# ExtendBoard.net
KiCad netlist of a schematic drawn in Altium Designer
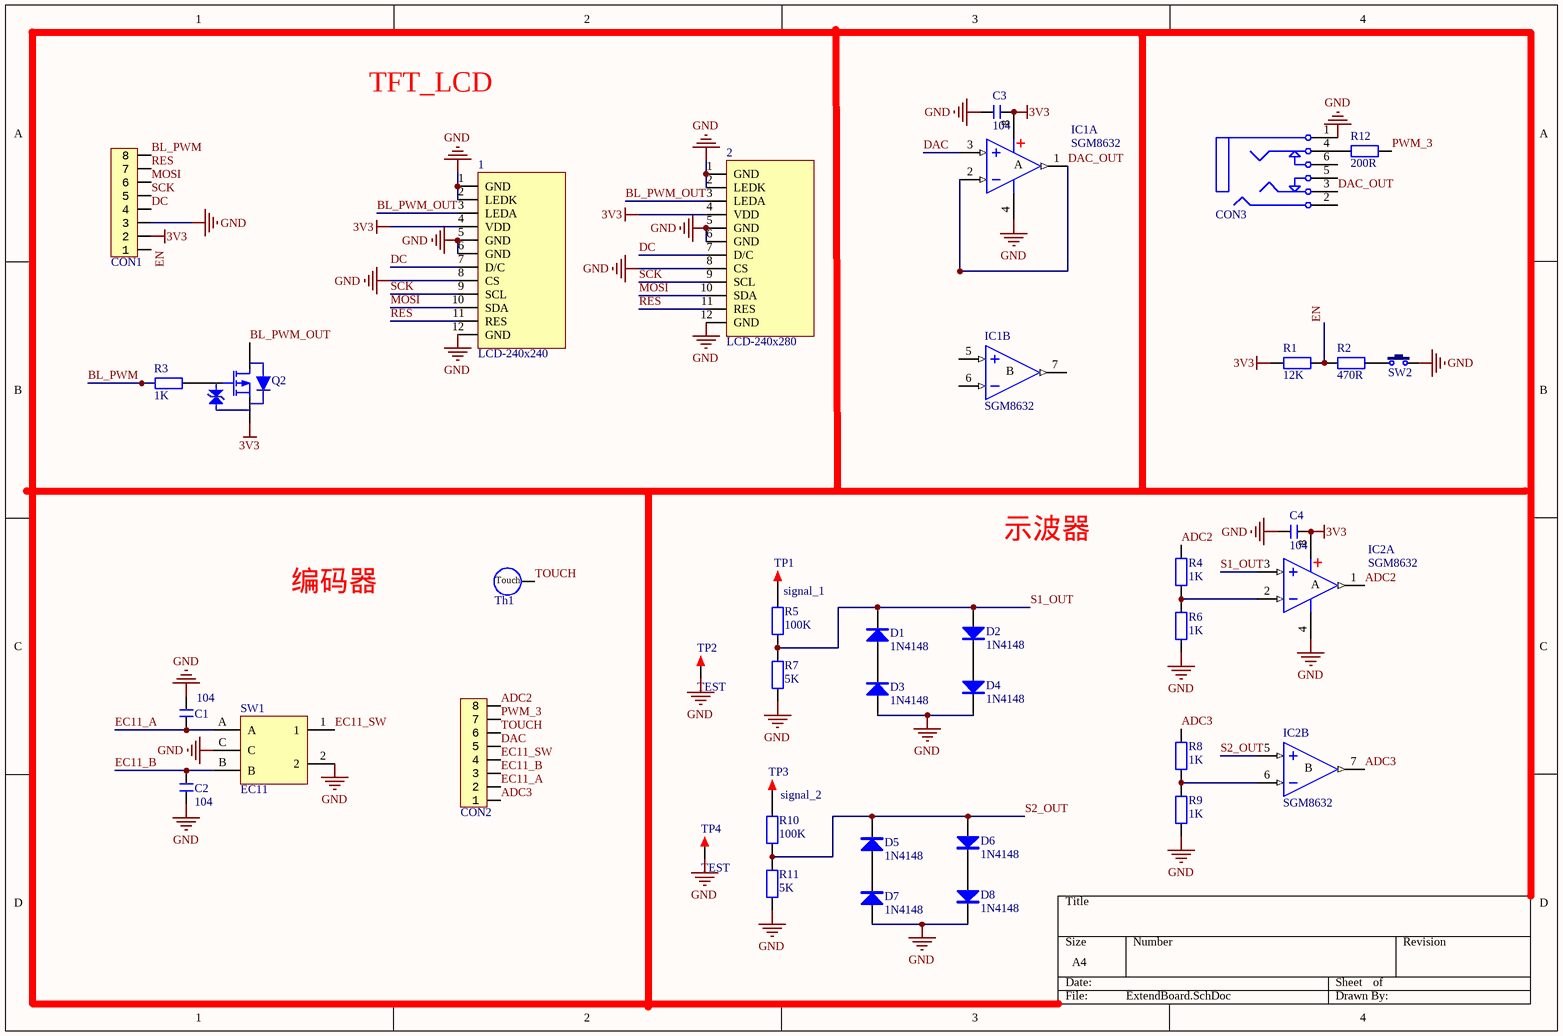
[diagram p0: ExtendBoard.SchDoc]

(export (version "E")
  (design (tool "Eeschema 10.0.6"))
  (components
    (comp (ref "1")
      (value "LCD-240x240")
      (footprint "LCD-240x240-NoHole")
      (description "显示屏")
      (libsource (lib "ExtendBoard") (part "LCD-240x240"))
    )
    (comp (ref "2")
      (value "LCD-240x280")
      (footprint "LCD-ST7789")
      (description "显示屏")
      (libsource (lib "ExtendBoard") (part "LCD-240x240"))
    )
    (comp (ref "C1")
      (value "104")
      (footprint "C 0603")
      (description "无极性贴片电容")
      (fields (field (name "版权归属") "源创客"))
      (libsource (lib "HeatPlatform") (part "C"))
    )
    (comp (ref "C2")
      (value "104")
      (footprint "C 0603")
      (description "无极性贴片电容")
      (fields (field (name "版权归属") "源创客"))
      (libsource (lib "HeatPlatform") (part "C"))
    )
    (comp (ref "C3")
      (value "104")
      (footprint "C 0603")
      (description "无极性贴片电容")
      (fields (field (name "版权归属") "源创客"))
      (libsource (lib "ExtendBoard") (part "C"))
    )
    (comp (ref "C4")
      (value "104")
      (footprint "C 0603")
      (description "无极性贴片电容")
      (fields (field (name "版权归属") "源创客"))
      (libsource (lib "ExtendBoard") (part "C"))
    )
    (comp (ref "CON1")
      (value "FFC_0.5_8")
      (footprint "FFC_0.5_8")
      (description "FFC")
      (libsource (lib "ExtendBoard") (part "FFC_0.5_8"))
    )
    (comp (ref "CON2")
      (value "FFC_0.5_8")
      (footprint "FFC_0.5_8")
      (description "FFC")
      (libsource (lib "ExtendBoard") (part "FFC_0.5_8"))
    )
    (comp (ref "CON3")
      (value "PJ342")
      (footprint "PJ342A")
      (description "3.5耳机插座,4Pin")
      (libsource (lib "ExtendBoard") (part "PJ342"))
    )
    (comp (ref "D1")
      (value "1N4148")
      (footprint "SOD-323")
      (description "高速开关二极管")
      (libsource (lib "ExtendBoard") (part "1N4148"))
    )
    (comp (ref "D2")
      (value "1N4148")
      (footprint "SOD-323")
      (description "高速开关二极管")
      (libsource (lib "ExtendBoard") (part "1N4148"))
    )
    (comp (ref "D3")
      (value "1N4148")
      (footprint "SOD-323")
      (description "高速开关二极管")
      (libsource (lib "ExtendBoard") (part "1N4148"))
    )
    (comp (ref "D4")
      (value "1N4148")
      (footprint "SOD-323")
      (description "高速开关二极管")
      (libsource (lib "ExtendBoard") (part "1N4148"))
    )
    (comp (ref "D5")
      (value "1N4148")
      (footprint "SOD-323")
      (description "高速开关二极管")
      (libsource (lib "ExtendBoard") (part "1N4148"))
    )
    (comp (ref "D6")
      (value "1N4148")
      (footprint "SOD-323")
      (description "高速开关二极管")
      (libsource (lib "ExtendBoard") (part "1N4148"))
    )
    (comp (ref "D7")
      (value "1N4148")
      (footprint "SOD-323")
      (description "高速开关二极管")
      (libsource (lib "ExtendBoard") (part "1N4148"))
    )
    (comp (ref "D8")
      (value "1N4148")
      (footprint "SOD-323")
      (description "高速开关二极管")
      (libsource (lib "ExtendBoard") (part "1N4148"))
    )
    (comp (ref "IC1")
      (value "SGM8632")
      (footprint "SOP8_N")
      (description "轨到轨双路运放")
      (libsource (lib "ExtendBoard") (part "SGM8632"))
    )
    (comp (ref "IC2")
      (value "SGM8632")
      (footprint "SOP8_N")
      (description "轨到轨双路运放")
      (libsource (lib "ExtendBoard") (part "SGM8632"))
    )
    (comp (ref "Q2")
      (value "AO3415A")
      (footprint "SOT23-3")
      (description "MOSFET")
      (fields (field (name "PUBLISHER") "Altium Limited"))
      (libsource (lib "ExtendBoard") (part "AO3415A"))
    )
    (comp (ref "R1")
      (value "12K")
      (footprint "R 0603")
      (description "贴片电阻")
      (fields (field (name "版权归属") "源创客"))
      (libsource (lib "ExtendBoard") (part "R"))
    )
    (comp (ref "R2")
      (value "470R")
      (footprint "R 0603")
      (description "贴片电阻")
      (fields (field (name "版权归属") "源创客"))
      (libsource (lib "ExtendBoard") (part "R"))
    )
    (comp (ref "R3")
      (value "1K")
      (footprint "R 0603")
      (description "贴片电阻")
      (fields (field (name "版权归属") "源创客"))
      (libsource (lib "HeatPlatform") (part "R"))
    )
    (comp (ref "R4")
      (value "1K")
      (footprint "R 0603")
      (description "贴片电阻")
      (fields (field (name "版权归属") "源创客"))
      (libsource (lib "ExtendBoard") (part "R"))
    )
    (comp (ref "R5")
      (value "100K")
      (footprint "R 0603")
      (description "贴片电阻")
      (fields (field (name "版权归属") "源创客"))
      (libsource (lib "ExtendBoard") (part "R"))
    )
    (comp (ref "R6")
      (value "1K")
      (footprint "R 0603")
      (description "贴片电阻")
      (fields (field (name "版权归属") "源创客"))
      (libsource (lib "ExtendBoard") (part "R"))
    )
    (comp (ref "R7")
      (value "5K")
      (footprint "R 0603")
      (description "贴片电阻")
      (fields (field (name "版权归属") "源创客"))
      (libsource (lib "ExtendBoard") (part "R"))
    )
    (comp (ref "R8")
      (value "1K")
      (footprint "R 0603")
      (description "贴片电阻")
      (fields (field (name "版权归属") "源创客"))
      (libsource (lib "ExtendBoard") (part "R"))
    )
    (comp (ref "R9")
      (value "1K")
      (footprint "R 0603")
      (description "贴片电阻")
      (fields (field (name "版权归属") "源创客"))
      (libsource (lib "ExtendBoard") (part "R"))
    )
    (comp (ref "R10")
      (value "100K")
      (footprint "R 0603")
      (description "贴片电阻")
      (fields (field (name "版权归属") "源创客"))
      (libsource (lib "ExtendBoard") (part "R"))
    )
    (comp (ref "R11")
      (value "5K")
      (footprint "R 0603")
      (description "贴片电阻")
      (fields (field (name "版权归属") "源创客"))
      (libsource (lib "ExtendBoard") (part "R"))
    )
    (comp (ref "R12")
      (value "200R")
      (footprint "R 0603")
      (description "贴片电阻")
      (fields (field (name "版权归属") "源创客"))
      (libsource (lib "ExtendBoard") (part "R"))
    )
    (comp (ref "SW1")
      (value "EC11")
      (footprint "EC11-DEEP")
      (description "数字开关编码器")
      (fields (field (name "版权归属") "源创客"))
      (libsource (lib "ExtendBoard") (part "EC11"))
    )
    (comp (ref "SW2")
      (value "3x6x5")
      (footprint "TSW 3*6*4.3-S-W")
      (description "3x6轻触开关")
      (fields (field (name "版权归属") "源创客"))
      (libsource (lib "ExtendBoard") (part "TSW 3x6"))
    )
    (comp (ref "Th1")
      (value "Touch 10X10mm")
      (footprint "Touch-5X5mm")
      (description "触控焊盘")
      (libsource (lib "ExtendBoard") (part "Touch-1P"))
    )
    (comp (ref "TP1")
      (value "signal_1")
      (footprint "TEST 2.0")
      (description "测试点")
      (libsource (lib "ExtendBoard") (part "TEST"))
    )
    (comp (ref "TP2")
      (value "TEST")
      (footprint "TEST 2.0")
      (description "测试点")
      (libsource (lib "ExtendBoard") (part "TEST"))
    )
    (comp (ref "TP3")
      (value "signal_2")
      (footprint "TEST 2.0")
      (description "测试点")
      (libsource (lib "ExtendBoard") (part "TEST"))
    )
    (comp (ref "TP4")
      (value "TEST")
      (footprint "TEST 2.0")
      (description "测试点")
      (libsource (lib "ExtendBoard") (part "TEST"))
    )
  )
  (nets
    (net (code "1") (name "/ADC2") (class "Default")
      (node (ref "CON2") (pin "8") (pinfunction "8_8") (pintype "passive"))
      (node (ref "IC2") (pin "1") (pinfunction "OUT_1") (pintype "output"))
      (node (ref "R4") (pin "2") (pinfunction "2_2") (pintype "passive"))
    )
    (net (code "2") (name "/ADC3") (class "Default")
      (node (ref "CON2") (pin "1") (pinfunction "1_1") (pintype "passive"))
      (node (ref "IC2") (pin "7") (pinfunction "OUT_7") (pintype "output"))
      (node (ref "R8") (pin "2") (pinfunction "2_2") (pintype "passive"))
    )
    (net (code "3") (name "/BL_PWM") (class "Default")
      (node (ref "CON1") (pin "8") (pinfunction "8_8") (pintype "passive"))
      (node (ref "R3") (pin "1") (pinfunction "1_1") (pintype "passive"))
    )
    (net (code "4") (name "/BL_PWM_OUT") (class "Default")
      (node (ref "1") (pin "3") (pinfunction "LEDA_3") (pintype "passive"))
      (node (ref "2") (pin "3") (pinfunction "LEDA_3") (pintype "passive"))
      (node (ref "Q2") (pin "3") (pinfunction "D_3") (pintype "passive"))
    )
    (net (code "5") (name "/DAC") (class "Default")
      (node (ref "CON2") (pin "5") (pinfunction "5_5") (pintype "passive"))
      (node (ref "IC1") (pin "3") (pinfunction "IN+_3") (pintype "input"))
    )
    (net (code "6") (name "/DAC_OUT") (class "Default")
      (node (ref "CON3") (pin "3") (pinfunction "3_3") (pintype "passive"))
      (node (ref "IC1") (pin "1") (pinfunction "OUT_1") (pintype "output"))
      (node (ref "IC1") (pin "2") (pinfunction "IN-_2") (pintype "input"))
    )
    (net (code "7") (name "/DC") (class "Default")
      (node (ref "1") (pin "7") (pinfunction "D/C_7") (pintype "passive"))
      (node (ref "2") (pin "7") (pinfunction "D/C_7") (pintype "passive"))
      (node (ref "CON1") (pin "4") (pinfunction "4_4") (pintype "passive"))
    )
    (net (code "8") (name "/EC11_A") (class "Default")
      (node (ref "C1") (pin "1") (pinfunction "1_1") (pintype "passive"))
      (node (ref "CON2") (pin "2") (pinfunction "2_2") (pintype "passive"))
      (node (ref "SW1") (pin "A") (pinfunction "A_A") (pintype "passive"))
    )
    (net (code "9") (name "/EC11_B") (class "Default")
      (node (ref "C2") (pin "2") (pinfunction "2_2") (pintype "passive"))
      (node (ref "CON2") (pin "3") (pinfunction "3_3") (pintype "passive"))
      (node (ref "SW1") (pin "B") (pinfunction "B_B") (pintype "passive"))
    )
    (net (code "10") (name "/EC11_SW") (class "Default")
      (node (ref "CON2") (pin "4") (pinfunction "4_4") (pintype "passive"))
      (node (ref "SW1") (pin "1") (pinfunction "1_1") (pintype "passive"))
    )
    (net (code "11") (name "/EN") (class "Default")
      (node (ref "CON1") (pin "1") (pinfunction "1_1") (pintype "passive"))
      (node (ref "R1") (pin "1") (pinfunction "1_1") (pintype "passive"))
      (node (ref "R2") (pin "2") (pinfunction "2_2") (pintype "passive"))
    )
    (net (code "12") (name "/MOSI") (class "Default")
      (node (ref "1") (pin "10") (pinfunction "SDA_10") (pintype "passive"))
      (node (ref "2") (pin "10") (pinfunction "SDA_10") (pintype "passive"))
      (node (ref "CON1") (pin "6") (pinfunction "6_6") (pintype "passive"))
    )
    (net (code "13") (name "/PWM_3") (class "Default")
      (node (ref "CON2") (pin "7") (pinfunction "7_7") (pintype "passive"))
      (node (ref "R12") (pin "2") (pinfunction "2_2") (pintype "passive"))
    )
    (net (code "14") (name "/RES") (class "Default")
      (node (ref "1") (pin "11") (pinfunction "RES_11") (pintype "passive"))
      (node (ref "2") (pin "11") (pinfunction "RES_11") (pintype "passive"))
      (node (ref "CON1") (pin "7") (pinfunction "7_7") (pintype "passive"))
    )
    (net (code "15") (name "/S1_OUT") (class "Default")
      (node (ref "D1") (pin "2") (pinfunction "K_2") (pintype "passive"))
      (node (ref "D2") (pin "1") (pinfunction "A_1") (pintype "passive"))
      (node (ref "IC2") (pin "3") (pinfunction "IN+_3") (pintype "input"))
      (node (ref "R5") (pin "1") (pinfunction "1_1") (pintype "passive"))
      (node (ref "R7") (pin "2") (pinfunction "2_2") (pintype "passive"))
    )
    (net (code "16") (name "/S2_OUT") (class "Default")
      (node (ref "D5") (pin "2") (pinfunction "K_2") (pintype "passive"))
      (node (ref "D6") (pin "1") (pinfunction "A_1") (pintype "passive"))
      (node (ref "IC2") (pin "5") (pinfunction "IN+_5") (pintype "input"))
      (node (ref "R10") (pin "1") (pinfunction "1_1") (pintype "passive"))
      (node (ref "R11") (pin "2") (pinfunction "2_2") (pintype "passive"))
    )
    (net (code "17") (name "/SCK") (class "Default")
      (node (ref "1") (pin "9") (pinfunction "SCL_9") (pintype "passive"))
      (node (ref "2") (pin "9") (pinfunction "SCL_9") (pintype "passive"))
      (node (ref "CON1") (pin "5") (pinfunction "5_5") (pintype "passive"))
    )
    (net (code "18") (name "/TOUCH") (class "Default")
      (node (ref "CON2") (pin "6") (pinfunction "6_6") (pintype "passive"))
      (node (ref "Th1") (pin "Touch") (pinfunction "Touch_Touch") (pintype "passive"))
    )
    (net (code "19") (name "3V3") (class "Default")
      (node (ref "1") (pin "4") (pinfunction "VDD_4") (pintype "passive"))
      (node (ref "2") (pin "4") (pinfunction "VDD_4") (pintype "passive"))
      (node (ref "C3") (pin "2") (pinfunction "2_2") (pintype "passive"))
      (node (ref "C4") (pin "2") (pinfunction "2_2") (pintype "passive"))
      (node (ref "CON1") (pin "2") (pinfunction "2_2") (pintype "passive"))
      (node (ref "IC1") (pin "8") (pinfunction "V+_8") (pintype "power_in"))
      (node (ref "IC2") (pin "8") (pinfunction "V+_8") (pintype "power_in"))
      (node (ref "Q2") (pin "2") (pinfunction "S_2") (pintype "passive"))
      (node (ref "R1") (pin "2") (pinfunction "2_2") (pintype "passive"))
    )
    (net (code "20") (name "GND") (class "Default")
      (node (ref "1") (pin "1") (pinfunction "GND_1") (pintype "passive"))
      (node (ref "1") (pin "12") (pinfunction "GND_12") (pintype "passive"))
      (node (ref "1") (pin "2") (pinfunction "LEDK_2") (pintype "passive"))
      (node (ref "1") (pin "5") (pinfunction "GND_5") (pintype "passive"))
      (node (ref "1") (pin "6") (pinfunction "GND_6") (pintype "passive"))
      (node (ref "1") (pin "8") (pinfunction "CS_8") (pintype "passive"))
      (node (ref "2") (pin "1") (pinfunction "GND_1") (pintype "passive"))
      (node (ref "2") (pin "12") (pinfunction "GND_12") (pintype "passive"))
      (node (ref "2") (pin "2") (pinfunction "LEDK_2") (pintype "passive"))
      (node (ref "2") (pin "5") (pinfunction "GND_5") (pintype "passive"))
      (node (ref "2") (pin "6") (pinfunction "GND_6") (pintype "passive"))
      (node (ref "2") (pin "8") (pinfunction "CS_8") (pintype "passive"))
      (node (ref "C1") (pin "2") (pinfunction "2_2") (pintype "passive"))
      (node (ref "C2") (pin "1") (pinfunction "1_1") (pintype "passive"))
      (node (ref "C3") (pin "1") (pinfunction "1_1") (pintype "passive"))
      (node (ref "C4") (pin "1") (pinfunction "1_1") (pintype "passive"))
      (node (ref "CON1") (pin "3") (pinfunction "3_3") (pintype "passive"))
      (node (ref "CON3") (pin "1") (pinfunction "1_1") (pintype "passive"))
      (node (ref "D3") (pin "1") (pinfunction "A_1") (pintype "passive"))
      (node (ref "D4") (pin "2") (pinfunction "K_2") (pintype "passive"))
      (node (ref "D7") (pin "1") (pinfunction "A_1") (pintype "passive"))
      (node (ref "D8") (pin "2") (pinfunction "K_2") (pintype "passive"))
      (node (ref "IC1") (pin "4") (pinfunction "V-_4") (pintype "power_in"))
      (node (ref "IC2") (pin "4") (pinfunction "V-_4") (pintype "power_in"))
      (node (ref "R11") (pin "1") (pinfunction "1_1") (pintype "passive"))
      (node (ref "R6") (pin "1") (pinfunction "1_1") (pintype "passive"))
      (node (ref "R7") (pin "1") (pinfunction "1_1") (pintype "passive"))
      (node (ref "R9") (pin "1") (pinfunction "1_1") (pintype "passive"))
      (node (ref "SW1") (pin "2") (pinfunction "2_2") (pintype "passive"))
      (node (ref "SW1") (pin "C") (pinfunction "C_C") (pintype "passive"))
      (node (ref "SW2") (pin "2") (pinfunction "2_2") (pintype "passive"))
      (node (ref "TP2") (pin "1") (pinfunction "1_1") (pintype "passive"))
      (node (ref "TP4") (pin "1") (pinfunction "1_1") (pintype "passive"))
    )
    (net (code "21") (name "Net-(CON3-Pad4)") (class "Default")
      (node (ref "CON3") (pin "4") (pinfunction "4_4") (pintype "passive"))
      (node (ref "R12") (pin "1") (pinfunction "1_1") (pintype "passive"))
    )
    (net (code "22") (name "Net-(D1-A)") (class "Default")
      (node (ref "D1") (pin "1") (pinfunction "A_1") (pintype "passive"))
      (node (ref "D3") (pin "2") (pinfunction "K_2") (pintype "passive"))
    )
    (net (code "23") (name "Net-(D2-K)") (class "Default")
      (node (ref "D2") (pin "2") (pinfunction "K_2") (pintype "passive"))
      (node (ref "D4") (pin "1") (pinfunction "A_1") (pintype "passive"))
    )
    (net (code "24") (name "Net-(D5-A)") (class "Default")
      (node (ref "D5") (pin "1") (pinfunction "A_1") (pintype "passive"))
      (node (ref "D7") (pin "2") (pinfunction "K_2") (pintype "passive"))
    )
    (net (code "25") (name "Net-(D6-K)") (class "Default")
      (node (ref "D6") (pin "2") (pinfunction "K_2") (pintype "passive"))
      (node (ref "D8") (pin "1") (pinfunction "A_1") (pintype "passive"))
    )
    (net (code "26") (name "Net-(IC2A-IN-)") (class "Default")
      (node (ref "IC2") (pin "2") (pinfunction "IN-_2") (pintype "input"))
      (node (ref "R4") (pin "1") (pinfunction "1_1") (pintype "passive"))
      (node (ref "R6") (pin "2") (pinfunction "2_2") (pintype "passive"))
    )
    (net (code "27") (name "Net-(IC2B-IN-)") (class "Default")
      (node (ref "IC2") (pin "6") (pinfunction "IN-_6") (pintype "input"))
      (node (ref "R8") (pin "1") (pinfunction "1_1") (pintype "passive"))
      (node (ref "R9") (pin "2") (pinfunction "2_2") (pintype "passive"))
    )
    (net (code "28") (name "Net-(Q2-G)") (class "Default")
      (node (ref "Q2") (pin "1") (pinfunction "G_1") (pintype "passive"))
      (node (ref "R3") (pin "2") (pinfunction "2_2") (pintype "passive"))
    )
    (net (code "29") (name "Net-(R2-Pad1)") (class "Default")
      (node (ref "R2") (pin "1") (pinfunction "1_1") (pintype "passive"))
      (node (ref "SW2") (pin "1") (pinfunction "1_1") (pintype "passive"))
    )
    (net (code "30") (name "Net-(R5-Pad2)") (class "Default")
      (node (ref "R5") (pin "2") (pinfunction "2_2") (pintype "passive"))
      (node (ref "TP1") (pin "1") (pinfunction "1_1") (pintype "passive"))
    )
    (net (code "31") (name "Net-(R10-Pad2)") (class "Default")
      (node (ref "R10") (pin "2") (pinfunction "2_2") (pintype "passive"))
      (node (ref "TP3") (pin "1") (pinfunction "1_1") (pintype "passive"))
    )
    (net (code "32") (name "unconnected-(CON3-Pad2)") (class "Default")
      (node (ref "CON3") (pin "2") (pinfunction "2_2") (pintype "passive"))
    )
    (net (code "33") (name "unconnected-(CON3-Pad5)") (class "Default")
      (node (ref "CON3") (pin "5") (pinfunction "5_5") (pintype "passive"))
    )
    (net (code "34") (name "unconnected-(CON3-Pad6)") (class "Default")
      (node (ref "CON3") (pin "6") (pinfunction "6_6") (pintype "passive"))
    )
    (net (code "35") (name "unconnected-(IC1B-IN+-Pad5)") (class "Default")
      (node (ref "IC1") (pin "5") (pinfunction "IN+_5") (pintype "input"))
    )
    (net (code "36") (name "unconnected-(IC1B-IN--Pad6)") (class "Default")
      (node (ref "IC1") (pin "6") (pinfunction "IN-_6") (pintype "input"))
    )
    (net (code "37") (name "unconnected-(IC1B-OUT-Pad7)") (class "Default")
      (node (ref "IC1") (pin "7") (pinfunction "OUT_7") (pintype "output"))
    )
  )
)
